# PICKIT2.net
KiCad netlist of a schematic drawn in Altium Designer
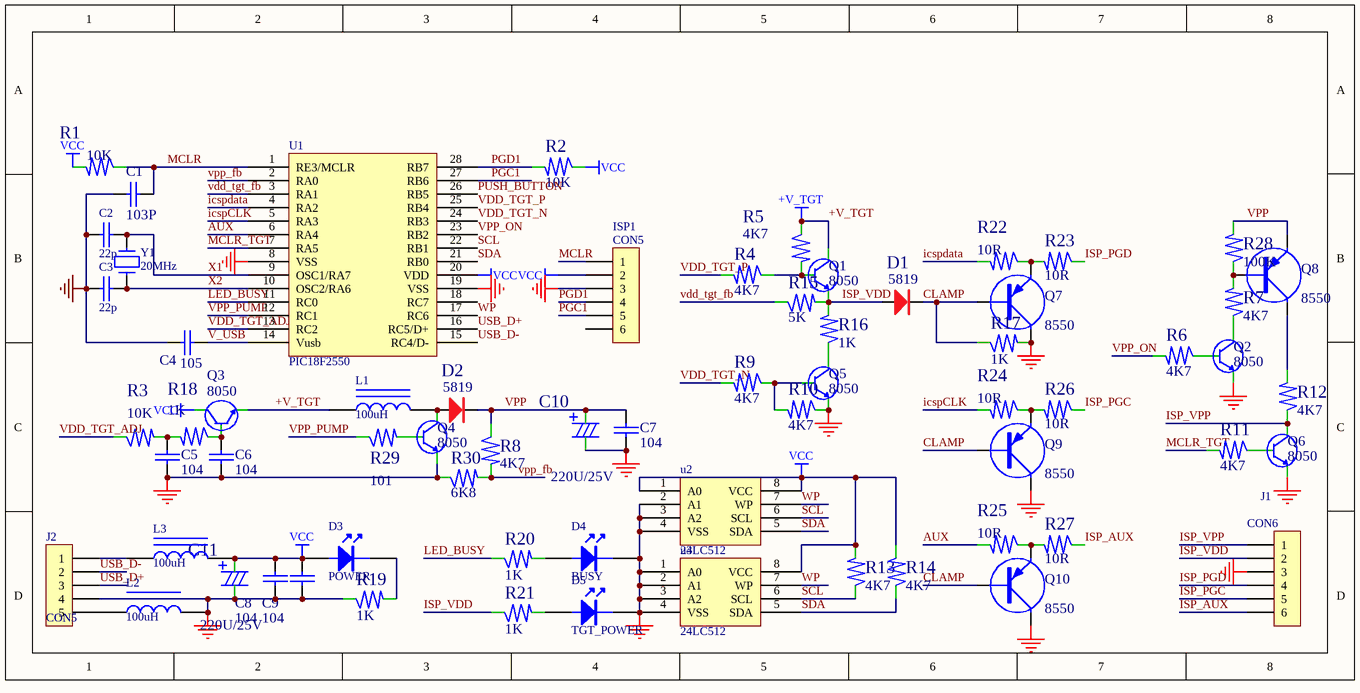
[diagram p0: PICKIT2.SchDoc]

(export (version "E")
  (design (tool "Eeschema 10.0.6"))
  (components
    (comp (ref "C1") (value "103P") (footprint "0603") (libsource (lib "*") (part "CAP")))
    (comp (ref "C2") (value "22p") (footprint "0603") (description "C") (libsource (lib "*") (part "CAP")))
    (comp (ref "C3") (value "22p") (footprint "0603") (description "C") (libsource (lib "*") (part "CAP")))
    (comp (ref "C4") (value "105") (footprint "0603") (libsource (lib "*") (part "CAP")))
    (comp (ref "C5") (value "104") (footprint "0603") (libsource (lib "*") (part "CAP")))
    (comp (ref "C6") (value "104") (footprint "0603") (libsource (lib "*") (part "CAP")))
    (comp (ref "C7") (value "104") (footprint "0603") (libsource (lib "*") (part "CAP")))
    (comp (ref "C8") (value "104") (footprint "0603") (libsource (lib "*") (part "CAP")))
    (comp (ref "C9") (value "104") (footprint "0603") (libsource (lib "*") (part "CAP")))
    (comp (ref "C10")
      (value "220U/25V")
      (footprint "3528")
      (description "ELECTROLYTIC CAPACITOR")
      (libsource (lib "*") (part "+CAP"))
    )
    (comp (ref "C11")
      (value "220U/25V")
      (footprint "3528")
      (description "ELECTROLYTIC CAPACITOR")
      (libsource (lib "*") (part "+CAP"))
    )
    (comp (ref "D1") (value "5819") (footprint "MLL34") (libsource (lib "*") (part "DIODE")))
    (comp (ref "D2") (value "5819") (footprint "MLL34") (libsource (lib "*") (part "DIODE")))
    (comp (ref "D3") (value "POWER") (footprint "0805-LED") (libsource (lib "*") (part "LED")))
    (comp (ref "D4") (value "BUSY") (footprint "0805-LED") (libsource (lib "*") (part "LED")))
    (comp (ref "D5") (value "TGT_POWER") (footprint "0805-LED") (libsource (lib "*") (part "LED")))
    (comp (ref "ISP1")
      (value "CON5")
      (footprint "SIP5")
      (description "Connector")
      (libsource (lib "*") (part "CON6"))
    )
    (comp (ref "J1")
      (value "CON6")
      (footprint "SIP6")
      (description "Connector")
      (libsource (lib "*") (part "CON6"))
    )
    (comp (ref "J2")
      (value "CON5")
      (footprint "sip5")
      (description "Connector")
      (libsource (lib "*") (part "CON5"))
    )
    (comp (ref "L1") (value "100uH") (footprint "rb.2/.4") (libsource (lib "*") (part "INDUCTOR IRON")))
    (comp (ref "L2") (value "100uH") (footprint "0805") (libsource (lib "*") (part "INDUCTOR IRON")))
    (comp (ref "L3") (value "100uH") (footprint "0805") (libsource (lib "*") (part "INDUCTOR IRON")))
    (comp (ref "Q1")
      (value "8050")
      (footprint "SOT-23")
      (description "NPN TRANSISTOR")
      (libsource (lib "") (part "NPN_1"))
    )
    (comp (ref "Q2")
      (value "8050")
      (footprint "SOT-23")
      (description "NPN TRANSISTOR")
      (libsource (lib "") (part "NPN_1"))
    )
    (comp (ref "Q3")
      (value "8050")
      (footprint "SOT-23")
      (description "NPN TRANSISTOR")
      (libsource (lib "*") (part "NPN"))
    )
    (comp (ref "Q4")
      (value "8050")
      (footprint "SOT-23")
      (description "NPN TRANSISTOR")
      (libsource (lib "") (part "NPN_1"))
    )
    (comp (ref "Q5")
      (value "8050")
      (footprint "SOT-23")
      (description "NPN TRANSISTOR")
      (libsource (lib "") (part "NPN_1"))
    )
    (comp (ref "Q6")
      (value "8050")
      (footprint "SOT-23")
      (description "NPN TRANSISTOR")
      (libsource (lib "") (part "NPN_1"))
    )
    (comp (ref "Q7") (value "8550") (footprint "SOT-23") (libsource (lib "*") (part "PNP")))
    (comp (ref "Q8") (value "8550") (footprint "SOT-23") (libsource (lib "*") (part "PNP")))
    (comp (ref "Q9") (value "8550") (footprint "SOT-23") (libsource (lib "*") (part "PNP")))
    (comp (ref "Q10") (value "8550") (footprint "SOT-23") (libsource (lib "*") (part "PNP")))
    (comp (ref "R1")
      (value "10K")
      (footprint "0603")
      (description "RESISTOR")
      (libsource (lib "*") (part "RES"))
    )
    (comp (ref "R2")
      (value "10K")
      (footprint "0603")
      (description "RESISTOR")
      (libsource (lib "*") (part "RES"))
    )
    (comp (ref "R3")
      (value "10K")
      (footprint "0603")
      (description "RESISTOR")
      (libsource (lib "*") (part "RES"))
    )
    (comp (ref "R4")
      (value "4K7")
      (footprint "0603")
      (description "RESISTOR")
      (libsource (lib "*") (part "RES"))
    )
    (comp (ref "R5")
      (value "4K7")
      (footprint "0603")
      (description "RESISTOR")
      (libsource (lib "*") (part "RES"))
    )
    (comp (ref "R6")
      (value "4K7")
      (footprint "0603")
      (description "RESISTOR")
      (libsource (lib "*") (part "RES"))
    )
    (comp (ref "R7")
      (value "4K7")
      (footprint "0603")
      (description "RESISTOR")
      (libsource (lib "*") (part "RES"))
    )
    (comp (ref "R8")
      (value "4K7")
      (footprint "0603")
      (description "RESISTOR")
      (libsource (lib "*") (part "RES"))
    )
    (comp (ref "R9")
      (value "4K7")
      (footprint "0603")
      (description "RESISTOR")
      (libsource (lib "*") (part "RES"))
    )
    (comp (ref "R10")
      (value "4K7")
      (footprint "0603")
      (description "RESISTOR")
      (libsource (lib "*") (part "RES"))
    )
    (comp (ref "R11")
      (value "4K7")
      (footprint "0603")
      (description "RESISTOR")
      (libsource (lib "*") (part "RES"))
    )
    (comp (ref "R12")
      (value "4K7")
      (footprint "0603")
      (description "RESISTOR")
      (libsource (lib "*") (part "RES"))
    )
    (comp (ref "R13")
      (value "4K7")
      (footprint "0603")
      (description "RESISTOR")
      (libsource (lib "*") (part "RES"))
    )
    (comp (ref "R14")
      (value "4K7")
      (footprint "0603")
      (description "RESISTOR")
      (libsource (lib "*") (part "RES"))
    )
    (comp (ref "R15")
      (value "5K")
      (footprint "0603")
      (description "RESISTOR")
      (libsource (lib "*") (part "RES"))
    )
    (comp (ref "R16")
      (value "1K")
      (footprint "0603")
      (description "RESISTOR")
      (libsource (lib "*") (part "RES"))
    )
    (comp (ref "R17")
      (value "1K")
      (footprint "0603")
      (description "RESISTOR")
      (libsource (lib "*") (part "RES"))
    )
    (comp (ref "R18")
      (value "1K")
      (footprint "0603")
      (description "RESISTOR")
      (libsource (lib "*") (part "RES"))
    )
    (comp (ref "R19")
      (value "1K")
      (footprint "0603")
      (description "RESISTOR")
      (libsource (lib "*") (part "RES"))
    )
    (comp (ref "R20")
      (value "1K")
      (footprint "0603")
      (description "RESISTOR")
      (libsource (lib "*") (part "RES"))
    )
    (comp (ref "R21")
      (value "1K")
      (footprint "0603")
      (description "RESISTOR")
      (libsource (lib "*") (part "RES"))
    )
    (comp (ref "R22")
      (value "10R")
      (footprint "0603")
      (description "RESISTOR")
      (libsource (lib "*") (part "RES"))
    )
    (comp (ref "R23")
      (value "10R")
      (footprint "0603")
      (description "RESISTOR")
      (libsource (lib "*") (part "RES"))
    )
    (comp (ref "R24")
      (value "10R")
      (footprint "0603")
      (description "RESISTOR")
      (libsource (lib "*") (part "RES"))
    )
    (comp (ref "R25")
      (value "10R")
      (footprint "0603")
      (description "RESISTOR")
      (libsource (lib "*") (part "RES"))
    )
    (comp (ref "R26")
      (value "10R")
      (footprint "0603")
      (description "RESISTOR")
      (libsource (lib "*") (part "RES"))
    )
    (comp (ref "R27")
      (value "10R")
      (footprint "0603")
      (description "RESISTOR")
      (libsource (lib "*") (part "RES"))
    )
    (comp (ref "R28")
      (value "100K")
      (footprint "0603")
      (description "RESISTOR")
      (libsource (lib "*") (part "RES"))
    )
    (comp (ref "R29")
      (value "101")
      (footprint "0603")
      (description "RESISTOR")
      (libsource (lib "*") (part "RES"))
    )
    (comp (ref "R30")
      (value "6K8")
      (footprint "0603")
      (description "RESISTOR")
      (libsource (lib "*") (part "RES"))
    )
    (comp (ref "U1") (value "PIC18F2550") (footprint "sol-28") (libsource (lib "*") (part "PIC18F2550")))
    (comp (ref "u2") (value "24LC512") (footprint "SO-8") (libsource (lib "*") (part "24LC512")))
    (comp (ref "u3") (value "24LC512") (footprint "SO-8") (libsource (lib "*") (part "24LC512")))
    (comp (ref "Y1")
      (value "20MHz")
      (footprint "smd5032")
      (description "Q")
      (libsource (lib "*") (part "CRYSTAL"))
    )
  )
  (nets
    (net (code "1") (name "+V_TGT") (class "Default")
      (node (ref "L1") (pin "1") (pinfunction "1_1") (pintype "passive"))
      (node (ref "Q1") (pin "C") (pinfunction "C_C") (pintype "passive"))
      (node (ref "Q3") (pin "E") (pinfunction "E_E") (pintype "passive"))
      (node (ref "R5") (pin "1") (pintype "passive"))
    )
    (net (code "2") (name "/AUX") (class "Default")
      (node (ref "R25") (pin "2") (pintype "passive"))
      (node (ref "U1") (pin "6") (pinfunction "RA4_6") (pintype "passive"))
    )
    (net (code "3") (name "/CLAMP") (class "Default")
      (node (ref "D1") (pin "K") (pintype "passive"))
      (node (ref "Q10") (pin "B") (pintype "passive"))
      (node (ref "Q7") (pin "B") (pintype "passive"))
      (node (ref "Q9") (pin "B") (pintype "passive"))
      (node (ref "R17") (pin "1") (pintype "passive"))
    )
    (net (code "4") (name "/ISP_AUX") (class "Default")
      (node (ref "J1") (pin "6") (pinfunction "6_6") (pintype "passive"))
      (node (ref "R27") (pin "1") (pintype "passive"))
    )
    (net (code "5") (name "/ISP_PGC") (class "Default")
      (node (ref "J1") (pin "5") (pinfunction "5_5") (pintype "passive"))
      (node (ref "R26") (pin "1") (pintype "passive"))
    )
    (net (code "6") (name "/ISP_PGD") (class "Default")
      (node (ref "J1") (pin "4") (pinfunction "4_4") (pintype "passive"))
      (node (ref "R23") (pin "1") (pintype "passive"))
    )
    (net (code "7") (name "/ISP_VDD") (class "Default")
      (node (ref "D1") (pin "A") (pintype "passive"))
      (node (ref "J1") (pin "2") (pinfunction "2_2") (pintype "passive"))
      (node (ref "Q1") (pin "E") (pinfunction "E_E") (pintype "passive"))
      (node (ref "R15") (pin "2") (pintype "passive"))
      (node (ref "R16") (pin "2") (pintype "passive"))
      (node (ref "R21") (pin "1") (pintype "passive"))
    )
    (net (code "8") (name "/ISP_VPP") (class "Default")
      (node (ref "J1") (pin "1") (pinfunction "1_1") (pintype "passive"))
      (node (ref "Q6") (pin "C") (pinfunction "C_C") (pintype "passive"))
      (node (ref "R12") (pin "1") (pintype "passive"))
    )
    (net (code "9") (name "/LED_BUSY") (class "Default")
      (node (ref "R20") (pin "1") (pintype "passive"))
      (node (ref "U1") (pin "11") (pinfunction "RC0_11") (pintype "passive"))
    )
    (net (code "10") (name "/MCLR") (class "Default")
      (node (ref "C1") (pin "2") (pintype "passive"))
      (node (ref "ISP1") (pin "1") (pinfunction "1_1") (pintype "passive"))
      (node (ref "R1") (pin "1") (pintype "passive"))
      (node (ref "U1") (pin "1") (pinfunction "RE3/MCLR_1") (pintype "passive"))
    )
    (net (code "11") (name "/MCLR_TGT") (class "Default")
      (node (ref "R11") (pin "2") (pintype "passive"))
      (node (ref "U1") (pin "7") (pinfunction "RA5_7") (pintype "passive"))
    )
    (net (code "12") (name "/PGC1") (class "Default")
      (node (ref "ISP1") (pin "5") (pinfunction "5_5") (pintype "passive"))
      (node (ref "U1") (pin "27") (pinfunction "RB6_27") (pintype "passive"))
    )
    (net (code "13") (name "/PGD1") (class "Default")
      (node (ref "ISP1") (pin "4") (pinfunction "4_4") (pintype "passive"))
      (node (ref "R2") (pin "2") (pintype "passive"))
      (node (ref "U1") (pin "28") (pinfunction "RB7_28") (pintype "passive"))
    )
    (net (code "14") (name "/PUSH_BUTTON") (class "Default")
      (node (ref "U1") (pin "26") (pinfunction "RB5_26") (pintype "passive"))
    )
    (net (code "15") (name "/SCL") (class "Default")
      (node (ref "R13") (pin "1") (pintype "passive"))
      (node (ref "U1") (pin "22") (pinfunction "RB1_22") (pintype "passive"))
      (node (ref "u2") (pin "6") (pinfunction "SCL_6") (pintype "passive"))
      (node (ref "u3") (pin "6") (pinfunction "SCL_6") (pintype "passive"))
    )
    (net (code "16") (name "/SDA") (class "Default")
      (node (ref "R14") (pin "1") (pintype "passive"))
      (node (ref "U1") (pin "21") (pinfunction "RB0_21") (pintype "passive"))
      (node (ref "u2") (pin "5") (pinfunction "SDA_5") (pintype "passive"))
      (node (ref "u3") (pin "5") (pinfunction "SDA_5") (pintype "passive"))
    )
    (net (code "17") (name "/USB_D+") (class "Default")
      (node (ref "J2") (pin "3") (pinfunction "3_3") (pintype "passive"))
      (node (ref "U1") (pin "16") (pinfunction "RC5/D+_16") (pintype "passive"))
    )
    (net (code "18") (name "/USB_D-") (class "Default")
      (node (ref "J2") (pin "2") (pinfunction "2_2") (pintype "passive"))
      (node (ref "U1") (pin "15") (pinfunction "RC4/D-_15") (pintype "passive"))
    )
    (net (code "19") (name "/VDD_TGT_ADJ") (class "Default")
      (node (ref "R3") (pin "1") (pintype "passive"))
      (node (ref "U1") (pin "13") (pinfunction "RC2_13") (pintype "passive"))
    )
    (net (code "20") (name "/VDD_TGT_N") (class "Default")
      (node (ref "R9") (pin "2") (pintype "passive"))
      (node (ref "U1") (pin "24") (pinfunction "RB3_24") (pintype "passive"))
    )
    (net (code "21") (name "/VDD_TGT_P") (class "Default")
      (node (ref "R4") (pin "2") (pintype "passive"))
      (node (ref "U1") (pin "25") (pinfunction "RB4_25") (pintype "passive"))
    )
    (net (code "22") (name "/VPP") (class "Default")
      (node (ref "C10") (pin "1") (pinfunction "1_1") (pintype "passive"))
      (node (ref "C7") (pin "2") (pintype "passive"))
      (node (ref "D2") (pin "K") (pintype "passive"))
      (node (ref "Q8") (pin "E") (pintype "passive"))
      (node (ref "R28") (pin "2") (pintype "passive"))
      (node (ref "R8") (pin "1") (pintype "passive"))
    )
    (net (code "23") (name "/VPP_ON") (class "Default")
      (node (ref "R6") (pin "2") (pintype "passive"))
      (node (ref "U1") (pin "23") (pinfunction "RB2_23") (pintype "passive"))
    )
    (net (code "24") (name "/VPP_PUMP") (class "Default")
      (node (ref "R29") (pin "1") (pintype "passive"))
      (node (ref "U1") (pin "12") (pinfunction "RC1_12") (pintype "passive"))
    )
    (net (code "25") (name "/V_USB") (class "Default")
      (node (ref "C4") (pin "1") (pintype "passive"))
      (node (ref "U1") (pin "14") (pinfunction "Vusb_14") (pintype "passive"))
    )
    (net (code "26") (name "/WP") (class "Default")
      (node (ref "U1") (pin "17") (pinfunction "RC6_17") (pintype "passive"))
      (node (ref "u2") (pin "7") (pinfunction "WP_7") (pintype "passive"))
      (node (ref "u3") (pin "7") (pinfunction "WP_7") (pintype "passive"))
    )
    (net (code "27") (name "/X1") (class "Default")
      (node (ref "C2") (pin "1") (pintype "passive"))
      (node (ref "U1") (pin "9") (pinfunction "OSC1/RA7_9") (pintype "passive"))
      (node (ref "Y1") (pin "1") (pintype "passive"))
    )
    (net (code "28") (name "/X2") (class "Default")
      (node (ref "C3") (pin "2") (pintype "passive"))
      (node (ref "U1") (pin "10") (pinfunction "OSC2/RA6_10") (pintype "passive"))
      (node (ref "Y1") (pin "2") (pintype "passive"))
    )
    (net (code "29") (name "/icspCLK") (class "Default")
      (node (ref "R24") (pin "2") (pintype "passive"))
      (node (ref "U1") (pin "5") (pinfunction "RA3_5") (pintype "passive"))
    )
    (net (code "30") (name "/icspdata") (class "Default")
      (node (ref "R22") (pin "2") (pintype "passive"))
      (node (ref "U1") (pin "4") (pinfunction "RA2_4") (pintype "passive"))
    )
    (net (code "31") (name "/vdd_tgt_fb") (class "Default")
      (node (ref "R15") (pin "1") (pintype "passive"))
      (node (ref "U1") (pin "3") (pinfunction "RA1_3") (pintype "passive"))
    )
    (net (code "32") (name "/vpp_fb") (class "Default")
      (node (ref "R30") (pin "2") (pintype "passive"))
      (node (ref "R8") (pin "2") (pintype "passive"))
      (node (ref "U1") (pin "2") (pinfunction "RA0_2") (pintype "passive"))
    )
    (net (code "33") (name "GND") (class "Default")
      (node (ref "C1") (pin "1") (pintype "passive"))
      (node (ref "C10") (pin "2") (pinfunction "2_2") (pintype "passive"))
      (node (ref "C11") (pin "2") (pinfunction "2_2") (pintype "passive"))
      (node (ref "C2") (pin "2") (pintype "passive"))
      (node (ref "C3") (pin "1") (pintype "passive"))
      (node (ref "C4") (pin "2") (pintype "passive"))
      (node (ref "C5") (pin "1") (pintype "passive"))
      (node (ref "C6") (pin "1") (pintype "passive"))
      (node (ref "C7") (pin "1") (pintype "passive"))
      (node (ref "C8") (pin "2") (pintype "passive"))
      (node (ref "C9") (pin "2") (pintype "passive"))
      (node (ref "D4") (pin "K") (pinfunction "2_K") (pintype "passive"))
      (node (ref "D5") (pin "K") (pinfunction "2_K") (pintype "passive"))
      (node (ref "ISP1") (pin "3") (pinfunction "3_3") (pintype "passive"))
      (node (ref "J1") (pin "3") (pinfunction "3_3") (pintype "passive"))
      (node (ref "J2") (pin "4") (pinfunction "4_4") (pintype "passive"))
      (node (ref "L2") (pin "2") (pinfunction "2_2") (pintype "passive"))
      (node (ref "Q10") (pin "C") (pintype "passive"))
      (node (ref "Q2") (pin "E") (pinfunction "E_E") (pintype "passive"))
      (node (ref "Q4") (pin "E") (pinfunction "E_E") (pintype "passive"))
      (node (ref "Q5") (pin "E") (pinfunction "E_E") (pintype "passive"))
      (node (ref "Q6") (pin "E") (pinfunction "E_E") (pintype "passive"))
      (node (ref "Q7") (pin "C") (pintype "passive"))
      (node (ref "Q9") (pin "C") (pintype "passive"))
      (node (ref "R10") (pin "1") (pintype "passive"))
      (node (ref "R17") (pin "2") (pintype "passive"))
      (node (ref "R19") (pin "1") (pintype "passive"))
      (node (ref "R30") (pin "1") (pintype "passive"))
      (node (ref "U1") (pin "19") (pinfunction "VSS_19") (pintype "passive"))
      (node (ref "U1") (pin "8") (pinfunction "VSS_8") (pintype "passive"))
      (node (ref "u2") (pin "2") (pinfunction "A1_2") (pintype "passive"))
      (node (ref "u2") (pin "3") (pinfunction "A2_3") (pintype "passive"))
      (node (ref "u2") (pin "4") (pinfunction "VSS_4") (pintype "passive"))
      (node (ref "u3") (pin "1") (pinfunction "A0_1") (pintype "passive"))
      (node (ref "u3") (pin "2") (pinfunction "A1_2") (pintype "passive"))
      (node (ref "u3") (pin "3") (pinfunction "A2_3") (pintype "passive"))
      (node (ref "u3") (pin "4") (pinfunction "VSS_4") (pintype "passive"))
    )
    (net (code "34") (name "Net-(C5-Pad2)") (class "Default")
      (node (ref "C5") (pin "2") (pintype "passive"))
      (node (ref "R18") (pin "2") (pintype "passive"))
      (node (ref "R3") (pin "2") (pintype "passive"))
    )
    (net (code "35") (name "Net-(C6-Pad2)") (class "Default")
      (node (ref "C6") (pin "2") (pintype "passive"))
      (node (ref "Q3") (pin "B") (pinfunction "B_B") (pintype "passive"))
      (node (ref "R18") (pin "1") (pintype "passive"))
    )
    (net (code "36") (name "Net-(D2-PadA)") (class "Default")
      (node (ref "D2") (pin "A") (pintype "passive"))
      (node (ref "L1") (pin "2") (pinfunction "2_2") (pintype "passive"))
      (node (ref "Q4") (pin "C") (pinfunction "C_C") (pintype "passive"))
    )
    (net (code "37") (name "Net-(D3-2)") (class "Default")
      (node (ref "D3") (pin "K") (pinfunction "2_K") (pintype "passive"))
      (node (ref "R19") (pin "2") (pintype "passive"))
    )
    (net (code "38") (name "Net-(D4-1)") (class "Default")
      (node (ref "D4") (pin "A") (pinfunction "1_A") (pintype "passive"))
      (node (ref "R20") (pin "2") (pintype "passive"))
    )
    (net (code "39") (name "Net-(D5-1)") (class "Default")
      (node (ref "D5") (pin "A") (pinfunction "1_A") (pintype "passive"))
      (node (ref "R21") (pin "2") (pintype "passive"))
    )
    (net (code "40") (name "Net-(J2-Pad1)") (class "Default")
      (node (ref "J2") (pin "1") (pinfunction "1_1") (pintype "passive"))
      (node (ref "L3") (pin "1") (pinfunction "1_1") (pintype "passive"))
    )
    (net (code "41") (name "Net-(J2-Pad5)") (class "Default")
      (node (ref "J2") (pin "5") (pinfunction "5_5") (pintype "passive"))
      (node (ref "L2") (pin "1") (pinfunction "1_1") (pintype "passive"))
    )
    (net (code "42") (name "Net-(Q1-PadB)") (class "Default")
      (node (ref "Q1") (pin "B") (pinfunction "B_B") (pintype "passive"))
      (node (ref "R4") (pin "1") (pintype "passive"))
      (node (ref "R5") (pin "2") (pintype "passive"))
    )
    (net (code "43") (name "Net-(Q2-PadB)") (class "Default")
      (node (ref "Q2") (pin "B") (pinfunction "B_B") (pintype "passive"))
      (node (ref "R6") (pin "1") (pintype "passive"))
    )
    (net (code "44") (name "Net-(Q2-PadC)") (class "Default")
      (node (ref "Q2") (pin "C") (pinfunction "C_C") (pintype "passive"))
      (node (ref "R7") (pin "1") (pintype "passive"))
    )
    (net (code "45") (name "Net-(Q4-PadB)") (class "Default")
      (node (ref "Q4") (pin "B") (pinfunction "B_B") (pintype "passive"))
      (node (ref "R29") (pin "2") (pintype "passive"))
    )
    (net (code "46") (name "Net-(Q5-PadB)") (class "Default")
      (node (ref "Q5") (pin "B") (pinfunction "B_B") (pintype "passive"))
      (node (ref "R10") (pin "2") (pintype "passive"))
      (node (ref "R9") (pin "1") (pintype "passive"))
    )
    (net (code "47") (name "Net-(Q5-PadC)") (class "Default")
      (node (ref "Q5") (pin "C") (pinfunction "C_C") (pintype "passive"))
      (node (ref "R16") (pin "1") (pintype "passive"))
    )
    (net (code "48") (name "Net-(Q6-PadB)") (class "Default")
      (node (ref "Q6") (pin "B") (pinfunction "B_B") (pintype "passive"))
      (node (ref "R11") (pin "1") (pintype "passive"))
    )
    (net (code "49") (name "Net-(Q7-PadE)") (class "Default")
      (node (ref "Q7") (pin "E") (pintype "passive"))
      (node (ref "R22") (pin "1") (pintype "passive"))
      (node (ref "R23") (pin "2") (pintype "passive"))
    )
    (net (code "50") (name "Net-(Q8-PadB)") (class "Default")
      (node (ref "Q8") (pin "B") (pintype "passive"))
      (node (ref "R28") (pin "1") (pintype "passive"))
      (node (ref "R7") (pin "2") (pintype "passive"))
    )
    (net (code "51") (name "Net-(Q8-PadC)") (class "Default")
      (node (ref "Q8") (pin "C") (pintype "passive"))
      (node (ref "R12") (pin "2") (pintype "passive"))
    )
    (net (code "52") (name "Net-(Q9-PadE)") (class "Default")
      (node (ref "Q9") (pin "E") (pintype "passive"))
      (node (ref "R24") (pin "1") (pintype "passive"))
      (node (ref "R26") (pin "2") (pintype "passive"))
    )
    (net (code "53") (name "Net-(Q10-PadE)") (class "Default")
      (node (ref "Q10") (pin "E") (pintype "passive"))
      (node (ref "R25") (pin "1") (pintype "passive"))
      (node (ref "R27") (pin "2") (pintype "passive"))
    )
    (net (code "54") (name "VCC") (class "Default")
      (node (ref "C11") (pin "1") (pinfunction "1_1") (pintype "passive"))
      (node (ref "C8") (pin "1") (pintype "passive"))
      (node (ref "C9") (pin "1") (pintype "passive"))
      (node (ref "D3") (pin "A") (pinfunction "1_A") (pintype "passive"))
      (node (ref "ISP1") (pin "2") (pinfunction "2_2") (pintype "passive"))
      (node (ref "L3") (pin "2") (pinfunction "2_2") (pintype "passive"))
      (node (ref "Q3") (pin "C") (pinfunction "C_C") (pintype "passive"))
      (node (ref "R1") (pin "2") (pintype "passive"))
      (node (ref "R13") (pin "2") (pintype "passive"))
      (node (ref "R14") (pin "2") (pintype "passive"))
      (node (ref "R2") (pin "1") (pintype "passive"))
      (node (ref "U1") (pin "20") (pinfunction "VDD_20") (pintype "passive"))
      (node (ref "u2") (pin "1") (pinfunction "A0_1") (pintype "passive"))
      (node (ref "u2") (pin "8") (pinfunction "VCC_8") (pintype "passive"))
      (node (ref "u3") (pin "8") (pinfunction "VCC_8") (pintype "passive"))
    )
    (net (code "55") (name "unconnected-(ISP1-Pad6)") (class "Default")
      (node (ref "ISP1") (pin "6") (pinfunction "6_6") (pintype "passive"))
    )
    (net (code "56") (name "unconnected-(U1-RC7-Pad18)") (class "Default")
      (node (ref "U1") (pin "18") (pinfunction "RC7_18") (pintype "passive"))
    )
  )
)
